# SCHEMATIC.net
KiCad netlist of a schematic drawn in Altium Designer
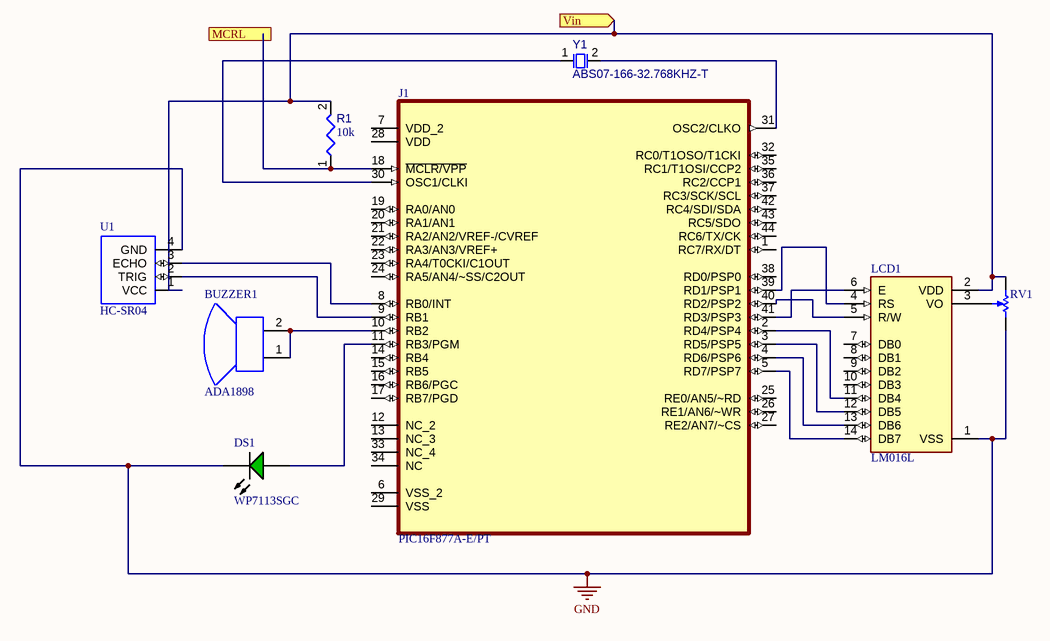
[diagram p0: SCHEMATIC.SchDoc]

(export (version "E")
  (design (tool "Eeschema 10.0.6"))
  (components
    (comp (ref "BUZZER1")
      (value "ADA1898")
      (footprint "ADAI-ADA1898")
      (description "Mini Speaker, 8 Ohm, 0.2 Wmax, -10 to 40 degC, 2-Pin THD, RoHS")
      (fields (field (name "MANUFACTURER") "Adafruit Industries"))
      (libsource (lib "Lê Nguyên") (part "SPEAKER-2"))
    )
    (comp (ref "DS1")
      (value "WP7113SGC")
      (footprint "KING-WP7113SGC_V")
      (description "The Super Bright Green Source Color Device, 2.2 V, -40 to 85 degC, 2-Pin THD, RoHS, Tape and Reel")
      (fields (field (name "MANUFACTURER") "Kingbright"))
      (libsource (lib "Lê Nguyên") (part "LED-GREEN-AK-2"))
    )
    (comp (ref "J1")
      (value "PIC16F877A-E/PT")
      (footprint "QFP80P1200X1200X120-44N")
      (description "7 KB Flash, 368 RAM, 33 I/O44 TQFP 10x10x1mm TRAY ¦ Microchip Technology Inc. PIC16F877A-E/PT")
      (fields (field (name "MF") "Microchip"))
      (libsource (lib "PIC16F877A-E_PT") (part "PIC16F877A-E/PT"))
    )
    (comp (ref "LCD1")
      (value "LM016L")
      (footprint "LCD_LM016L")
      (description "Display Lcd 35x75mm")
      (fields (field (name "MF") "Hitachi"))
      (libsource (lib "LM016L") (part "LM016L"))
    )
    (comp (ref "R1")
      (value "10k")
      (footprint "RESC3216X60X45ML15T20")
      (description "Chip Resistor, 10 KOhm, +/- 1%, 0.25 W, -55 to 155 degC, 1206 (3216 Metric)")
      (fields (field (name "TOLERANCE") "1%") (field (name "POWER") "250mW"))
      (libsource (lib "Lê Nguyên") (part "RES-2"))
    )
    (comp (ref "RV1")
      (value "TC33X-2-103E")
      (footprint "BOUR-TC33X-2_V")
      (description "Trimming Potentiometer, 1000 Ohm, -40 to 100 degC, 3-Pin SMD, RoHS, Tape and Reel")
      (fields (field (name "TOLERANCE") "25%") (field (name "POWER") "100mW"))
      (libsource (lib "Lê Nguyên") (part "RES-ADJ-3_A"))
    )
    (comp (ref "U1")
      (value "HC-SR04")
      (footprint "XCVR_HC-SR04")
      (description "Ultrasonic Sensor Module")
      (libsource (lib "HC-SR04") (part "HC-SR04"))
    )
    (comp (ref "Y1")
      (value "ABS07-166-32.768KHZ-T")
      (footprint "EPSON-FC-135_V")
      (description "Crystal 32.768kHz 10ppm 7pF -40C +85C")
      (libsource (lib "Lê Nguyên") (part "CMP-001-0024-1"))
    )
  )
  (nets
    (net (code "2") (name "/Vin") (class "Default")
      (node (ref "LCD1") (pin "2") (pinfunction "VDD_2") (pintype "power_in"))
      (node (ref "R1") (pin "2") (pinfunction "2_2") (pintype "passive"))
      (node (ref "RV1") (pin "1") (pinfunction "1_1") (pintype "passive"))
      (node (ref "U1") (pin "1") (pinfunction "VCC_1") (pintype "power_in"))
    )
    (net (code "3") (name "GND") (class "Default")
      (node (ref "DS1") (pin "2") (pinfunction "K_2") (pintype "passive"))
      (node (ref "LCD1") (pin "1") (pinfunction "VSS_1") (pintype "power_in"))
      (node (ref "RV1") (pin "3") (pinfunction "3_3") (pintype "passive"))
      (node (ref "U1") (pin "4") (pinfunction "GND_4") (pintype "power_in"))
    )
    (net (code "4") (name "Net-(BUZZER1-+)") (class "Default")
      (node (ref "BUZZER1") (pin "1") (pinfunction "+_1") (pintype "passive"))
      (node (ref "BUZZER1") (pin "2") (pinfunction "-_2") (pintype "passive"))
      (node (ref "J1") (pin "10") (pinfunction "RB2_10") (pintype "bidirectional"))
    )
    (net (code "5") (name "Net-(DS1-A)") (class "Default")
      (node (ref "DS1") (pin "1") (pinfunction "A_1") (pintype "passive"))
      (node (ref "J1") (pin "11") (pinfunction "RB3/PGM_11") (pintype "bidirectional"))
    )
    (net (code "6") (name "Net-(J1-OSC1{slash}CLKI)") (class "Default")
      (node (ref "J1") (pin "30") (pinfunction "OSC1/CLKI_30") (pintype "input"))
      (node (ref "Y1") (pin "1") (pinfunction "1_1") (pintype "passive"))
    )
    (net (code "7") (name "Net-(J1-OSC2{slash}CLKO)") (class "Default")
      (node (ref "J1") (pin "31") (pinfunction "OSC2/CLKO_31") (pintype "output"))
      (node (ref "Y1") (pin "2") (pinfunction "2_2") (pintype "passive"))
    )
    (net (code "8") (name "Net-(J1-RB0{slash}INT)") (class "Default")
      (node (ref "J1") (pin "8") (pinfunction "RB0/INT_8") (pintype "bidirectional"))
      (node (ref "U1") (pin "3") (pinfunction "ECHO_3") (pintype "bidirectional"))
    )
    (net (code "9") (name "Net-(J1-RB1)") (class "Default")
      (node (ref "J1") (pin "9") (pinfunction "RB1_9") (pintype "bidirectional"))
      (node (ref "U1") (pin "2") (pinfunction "TRIG_2") (pintype "bidirectional"))
    )
    (net (code "10") (name "Net-(J1-RD1{slash}PSP1)") (class "Default")
      (node (ref "J1") (pin "39") (pinfunction "RD1/PSP1_39") (pintype "bidirectional"))
      (node (ref "LCD1") (pin "4") (pinfunction "RS_4") (pintype "input"))
    )
    (net (code "11") (name "Net-(J1-RD2{slash}PSP2)") (class "Default")
      (node (ref "J1") (pin "40") (pinfunction "RD2/PSP2_40") (pintype "bidirectional"))
      (node (ref "LCD1") (pin "5") (pinfunction "R/W_5") (pintype "input"))
    )
    (net (code "12") (name "Net-(J1-RD3{slash}PSP3)") (class "Default")
      (node (ref "J1") (pin "41") (pinfunction "RD3/PSP3_41") (pintype "bidirectional"))
      (node (ref "LCD1") (pin "6") (pinfunction "E_6") (pintype "input"))
    )
    (net (code "13") (name "Net-(J1-RD4{slash}PSP4)") (class "Default")
      (node (ref "J1") (pin "2") (pinfunction "RD4/PSP4_2") (pintype "bidirectional"))
      (node (ref "LCD1") (pin "11") (pinfunction "DB4_11") (pintype "bidirectional"))
    )
    (net (code "14") (name "Net-(J1-RD5{slash}PSP5)") (class "Default")
      (node (ref "J1") (pin "3") (pinfunction "RD5/PSP5_3") (pintype "bidirectional"))
      (node (ref "LCD1") (pin "12") (pinfunction "DB5_12") (pintype "bidirectional"))
    )
    (net (code "15") (name "Net-(J1-RD6{slash}PSP6)") (class "Default")
      (node (ref "J1") (pin "4") (pinfunction "RD6/PSP6_4") (pintype "bidirectional"))
      (node (ref "LCD1") (pin "13") (pinfunction "DB6_13") (pintype "bidirectional"))
    )
    (net (code "16") (name "Net-(J1-RD7{slash}PSP7)") (class "Default")
      (node (ref "J1") (pin "5") (pinfunction "RD7/PSP7_5") (pintype "bidirectional"))
      (node (ref "LCD1") (pin "14") (pinfunction "DB7_14") (pintype "bidirectional"))
    )
    (net (code "17") (name "Net-(J1-~{MCLR{slash}VPP})") (class "Default")
      (node (ref "J1") (pin "18") (pinfunction "~{MCLR/VPP}_18") (pintype "input"))
      (node (ref "R1") (pin "1") (pinfunction "1_1") (pintype "passive"))
    )
    (net (code "18") (name "Net-(LCD1-VO)") (class "Default")
      (node (ref "LCD1") (pin "3") (pinfunction "VO_3") (pintype "power_in"))
      (node (ref "RV1") (pin "2") (pinfunction "2_2") (pintype "passive"))
    )
    (net (code "19") (name "unconnected-(J1-NC-Pad34)") (class "Default")
      (node (ref "J1") (pin "34") (pinfunction "NC_34") (pintype "passive"))
    )
    (net (code "20") (name "unconnected-(J1-NC_2-Pad12)") (class "Default")
      (node (ref "J1") (pin "12") (pinfunction "NC_2_12") (pintype "passive"))
    )
    (net (code "21") (name "unconnected-(J1-NC_3-Pad13)") (class "Default")
      (node (ref "J1") (pin "13") (pinfunction "NC_3_13") (pintype "passive"))
    )
    (net (code "22") (name "unconnected-(J1-NC_4-Pad33)") (class "Default")
      (node (ref "J1") (pin "33") (pinfunction "NC_4_33") (pintype "passive"))
    )
    (net (code "23") (name "unconnected-(J1-RA0{slash}AN0-Pad19)") (class "Default")
      (node (ref "J1") (pin "19") (pinfunction "RA0/AN0_19") (pintype "bidirectional"))
    )
    (net (code "24") (name "unconnected-(J1-RA1{slash}AN1-Pad20)") (class "Default")
      (node (ref "J1") (pin "20") (pinfunction "RA1/AN1_20") (pintype "bidirectional"))
    )
    (net (code "25") (name "unconnected-(J1-RA2{slash}AN2{slash}VREF-{slash}CVREF-Pad21)") (class "Default")
      (node (ref "J1") (pin "21") (pinfunction "RA2/AN2/VREF-/CVREF_21") (pintype "bidirectional"))
    )
    (net (code "26") (name "unconnected-(J1-RA3{slash}AN3{slash}VREF+-Pad22)") (class "Default")
      (node (ref "J1") (pin "22") (pinfunction "RA3/AN3/VREF+_22") (pintype "bidirectional"))
    )
    (net (code "27") (name "unconnected-(J1-RA4{slash}T0CKI{slash}C1OUT-Pad23)") (class "Default")
      (node (ref "J1") (pin "23") (pinfunction "RA4/T0CKI/C1OUT_23") (pintype "bidirectional"))
    )
    (net (code "28") (name "unconnected-(J1-RA5{slash}AN4{slash}~SS{slash}C2OUT-Pad24)") (class "Default")
      (node (ref "J1") (pin "24") (pinfunction "RA5/AN4/~SS/C2OUT_24") (pintype "bidirectional"))
    )
    (net (code "29") (name "unconnected-(J1-RB4-Pad14)") (class "Default")
      (node (ref "J1") (pin "14") (pinfunction "RB4_14") (pintype "bidirectional"))
    )
    (net (code "30") (name "unconnected-(J1-RB5-Pad15)") (class "Default")
      (node (ref "J1") (pin "15") (pinfunction "RB5_15") (pintype "bidirectional"))
    )
    (net (code "31") (name "unconnected-(J1-RB6{slash}PGC-Pad16)") (class "Default")
      (node (ref "J1") (pin "16") (pinfunction "RB6/PGC_16") (pintype "bidirectional"))
    )
    (net (code "32") (name "unconnected-(J1-RB7{slash}PGD-Pad17)") (class "Default")
      (node (ref "J1") (pin "17") (pinfunction "RB7/PGD_17") (pintype "bidirectional"))
    )
    (net (code "33") (name "unconnected-(J1-RC0{slash}T1OSO{slash}T1CKI-Pad32)") (class "Default")
      (node (ref "J1") (pin "32") (pinfunction "RC0/T1OSO/T1CKI_32") (pintype "bidirectional"))
    )
    (net (code "34") (name "unconnected-(J1-RC1{slash}T1OSI{slash}CCP2-Pad35)") (class "Default")
      (node (ref "J1") (pin "35") (pinfunction "RC1/T1OSI/CCP2_35") (pintype "bidirectional"))
    )
    (net (code "35") (name "unconnected-(J1-RC2{slash}CCP1-Pad36)") (class "Default")
      (node (ref "J1") (pin "36") (pinfunction "RC2/CCP1_36") (pintype "bidirectional"))
    )
    (net (code "36") (name "unconnected-(J1-RC3{slash}SCK{slash}SCL-Pad37)") (class "Default")
      (node (ref "J1") (pin "37") (pinfunction "RC3/SCK/SCL_37") (pintype "bidirectional"))
    )
    (net (code "37") (name "unconnected-(J1-RC4{slash}SDI{slash}SDA-Pad42)") (class "Default")
      (node (ref "J1") (pin "42") (pinfunction "RC4/SDI/SDA_42") (pintype "bidirectional"))
    )
    (net (code "38") (name "unconnected-(J1-RC5{slash}SDO-Pad43)") (class "Default")
      (node (ref "J1") (pin "43") (pinfunction "RC5/SDO_43") (pintype "bidirectional"))
    )
    (net (code "39") (name "unconnected-(J1-RC6{slash}TX{slash}CK-Pad44)") (class "Default")
      (node (ref "J1") (pin "44") (pinfunction "RC6/TX/CK_44") (pintype "bidirectional"))
    )
    (net (code "40") (name "unconnected-(J1-RC7{slash}RX{slash}DT-Pad1)") (class "Default")
      (node (ref "J1") (pin "1") (pinfunction "RC7/RX/DT_1") (pintype "bidirectional"))
    )
    (net (code "41") (name "unconnected-(J1-RD0{slash}PSP0-Pad38)") (class "Default")
      (node (ref "J1") (pin "38") (pinfunction "RD0/PSP0_38") (pintype "bidirectional"))
    )
    (net (code "42") (name "unconnected-(J1-RE0{slash}AN5{slash}~RD-Pad25)") (class "Default")
      (node (ref "J1") (pin "25") (pinfunction "RE0/AN5/~RD_25") (pintype "bidirectional"))
    )
    (net (code "43") (name "unconnected-(J1-RE1{slash}AN6{slash}~WR-Pad26)") (class "Default")
      (node (ref "J1") (pin "26") (pinfunction "RE1/AN6/~WR_26") (pintype "bidirectional"))
    )
    (net (code "44") (name "unconnected-(J1-RE2{slash}AN7{slash}~CS-Pad27)") (class "Default")
      (node (ref "J1") (pin "27") (pinfunction "RE2/AN7/~CS_27") (pintype "bidirectional"))
    )
    (net (code "45") (name "unconnected-(J1-VDD-Pad28)") (class "Default")
      (node (ref "J1") (pin "28") (pinfunction "VDD_28") (pintype "power_in"))
    )
    (net (code "46") (name "unconnected-(J1-VDD_2-Pad7)") (class "Default")
      (node (ref "J1") (pin "7") (pinfunction "VDD_2_7") (pintype "power_in"))
    )
    (net (code "47") (name "unconnected-(J1-VSS-Pad29)") (class "Default")
      (node (ref "J1") (pin "29") (pinfunction "VSS_29") (pintype "power_in"))
    )
    (net (code "48") (name "unconnected-(J1-VSS_2-Pad6)") (class "Default")
      (node (ref "J1") (pin "6") (pinfunction "VSS_2_6") (pintype "power_in"))
    )
    (net (code "49") (name "unconnected-(LCD1-DB0-Pad7)") (class "Default")
      (node (ref "LCD1") (pin "7") (pinfunction "DB0_7") (pintype "bidirectional"))
    )
    (net (code "50") (name "unconnected-(LCD1-DB1-Pad8)") (class "Default")
      (node (ref "LCD1") (pin "8") (pinfunction "DB1_8") (pintype "bidirectional"))
    )
    (net (code "51") (name "unconnected-(LCD1-DB2-Pad9)") (class "Default")
      (node (ref "LCD1") (pin "9") (pinfunction "DB2_9") (pintype "bidirectional"))
    )
    (net (code "52") (name "unconnected-(LCD1-DB3-Pad10)") (class "Default")
      (node (ref "LCD1") (pin "10") (pinfunction "DB3_10") (pintype "bidirectional"))
    )
  )
)
